# cpu-card-atmega328.net
KiCad netlist of a schematic drawn in EAGLE
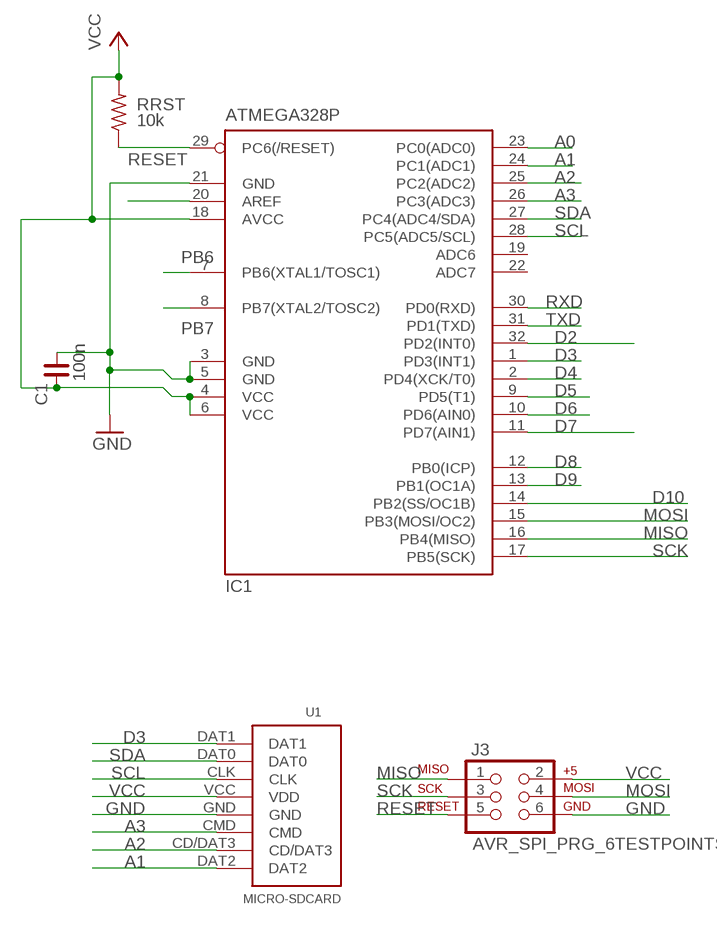
[diagram p0: schematic, sheet 1]

(export (version "E")
  (design (tool "Eeschema 10.0.6"))
  (components
    (comp (ref "C1")
      (value "100n")
      (footprint "eagle-import:C0603")
      (libsource (lib "eagle-import") (part "C_0603"))
    )
    (comp (ref "IC1")
      (value "ATMEGA328P")
      (footprint "eagle-import:TQFP32-08")
      (fields (field (name "MPN") "ATMEGA8-16AU"))
      (libsource (lib "eagle-import") (part "MEGA8-AI"))
    )
    (comp (ref "J3")
      (value "AVR_SPI_PRG_6TESTPOINTS")
      (footprint "eagle-import:2X3_TEST_POINTS")
      (libsource (lib "eagle-import") (part "AVR_SPI_PRG_6TESTPOINTS"))
    )
    (comp (ref "RRST")
      (value "10k")
      (footprint "eagle-import:R0603@1")
      (libsource (lib "eagle-import") (part "R-US_R0603"))
    )
    (comp (ref "U1")
      (value "MICRO-SDCARD")
      (footprint "eagle-import:MICRO-SDCARD")
      (libsource (lib "eagle-import") (part "MICRO-SDCARD"))
    )
  )
  (nets
    (net (code "1") (name "/A0") (class "Default")
      (node (ref "IC1") (pin "23") (pinfunction "PC0(ADC0)_23") (pintype "bidirectional"))
    )
    (net (code "2") (name "/A1") (class "Default")
      (node (ref "IC1") (pin "24") (pinfunction "PC1(ADC1)_24") (pintype "bidirectional"))
      (node (ref "U1") (pin "DAT2") (pinfunction "DAT2_DAT2") (pintype "bidirectional"))
    )
    (net (code "3") (name "/A2") (class "Default")
      (node (ref "IC1") (pin "25") (pinfunction "PC2(ADC2)_25") (pintype "bidirectional"))
      (node (ref "U1") (pin "CD/DAT3") (pinfunction "CD/DAT3_CD/DAT3") (pintype "bidirectional"))
    )
    (net (code "4") (name "/A3") (class "Default")
      (node (ref "IC1") (pin "26") (pinfunction "PC3(ADC3)_26") (pintype "bidirectional"))
      (node (ref "U1") (pin "CMD") (pinfunction "CMD_CMD") (pintype "bidirectional"))
    )
    (net (code "5") (name "/D2") (class "Default")
      (node (ref "IC1") (pin "32") (pinfunction "PD2(INT0)_32") (pintype "bidirectional"))
    )
    (net (code "6") (name "/D3") (class "Default")
      (node (ref "IC1") (pin "1") (pinfunction "PD3(INT1)_1") (pintype "bidirectional"))
      (node (ref "U1") (pin "DAT1") (pinfunction "DAT1_DAT1") (pintype "bidirectional"))
    )
    (net (code "7") (name "/D4") (class "Default")
      (node (ref "IC1") (pin "2") (pinfunction "PD4(XCK/T0)_2") (pintype "bidirectional"))
    )
    (net (code "8") (name "/D5") (class "Default")
      (node (ref "IC1") (pin "9") (pinfunction "PD5(T1)_9") (pintype "bidirectional"))
    )
    (net (code "9") (name "/D6") (class "Default")
      (node (ref "IC1") (pin "10") (pinfunction "PD6(AIN0)_10") (pintype "bidirectional"))
    )
    (net (code "10") (name "/D7") (class "Default")
      (node (ref "IC1") (pin "11") (pinfunction "PD7(AIN1)_11") (pintype "bidirectional"))
    )
    (net (code "11") (name "/D8") (class "Default")
      (node (ref "IC1") (pin "12") (pinfunction "PB0(ICP)_12") (pintype "bidirectional"))
    )
    (net (code "12") (name "/D9") (class "Default")
      (node (ref "IC1") (pin "13") (pinfunction "PB1(OC1A)_13") (pintype "bidirectional"))
    )
    (net (code "13") (name "/D10") (class "Default")
      (node (ref "IC1") (pin "14") (pinfunction "PB2(SS/OC1B)_14") (pintype "bidirectional"))
    )
    (net (code "14") (name "/MISO") (class "Default")
      (node (ref "IC1") (pin "16") (pinfunction "PB4(MISO)_16") (pintype "bidirectional"))
      (node (ref "J3") (pin "1") (pinfunction "1_1") (pintype "passive"))
    )
    (net (code "15") (name "/MOSI") (class "Default")
      (node (ref "IC1") (pin "15") (pinfunction "PB3(MOSI/OC2)_15") (pintype "bidirectional"))
      (node (ref "J3") (pin "4") (pinfunction "4_4") (pintype "passive"))
    )
    (net (code "16") (name "/PB6") (class "Default")
      (node (ref "IC1") (pin "7") (pinfunction "PB6(XTAL1/TOSC1)_7") (pintype "bidirectional"))
    )
    (net (code "17") (name "/PB7") (class "Default")
      (node (ref "IC1") (pin "8") (pinfunction "PB7(XTAL2/TOSC2)_8") (pintype "bidirectional"))
    )
    (net (code "18") (name "/RESET") (class "Default")
      (node (ref "IC1") (pin "29") (pinfunction "PC6(/RESET)_29") (pintype "bidirectional"))
      (node (ref "J3") (pin "5") (pinfunction "5_5") (pintype "passive"))
      (node (ref "RRST") (pin "1") (pinfunction "1_1") (pintype "passive"))
    )
    (net (code "19") (name "/RXD") (class "Default")
      (node (ref "IC1") (pin "30") (pinfunction "PD0(RXD)_30") (pintype "bidirectional"))
    )
    (net (code "20") (name "/SCK") (class "Default")
      (node (ref "IC1") (pin "17") (pinfunction "PB5(SCK)_17") (pintype "bidirectional"))
      (node (ref "J3") (pin "3") (pinfunction "3_3") (pintype "passive"))
    )
    (net (code "21") (name "/SCL") (class "Default")
      (node (ref "IC1") (pin "28") (pinfunction "PC5(ADC5/SCL)_28") (pintype "bidirectional"))
      (node (ref "U1") (pin "CLK") (pinfunction "CLK_CLK") (pintype "bidirectional"))
    )
    (net (code "22") (name "/SDA") (class "Default")
      (node (ref "IC1") (pin "27") (pinfunction "PC4(ADC4/SDA)_27") (pintype "bidirectional"))
      (node (ref "U1") (pin "DAT0") (pinfunction "DAT0_DAT0") (pintype "bidirectional"))
    )
    (net (code "23") (name "/TXD") (class "Default")
      (node (ref "IC1") (pin "31") (pinfunction "PD1(TXD)_31") (pintype "bidirectional"))
    )
    (net (code "24") (name "GND") (class "Default")
      (node (ref "C1") (pin "1") (pinfunction "1_1") (pintype "passive"))
      (node (ref "IC1") (pin "21") (pinfunction "GND_21") (pintype "power_in"))
      (node (ref "IC1") (pin "3") (pinfunction "GND_3") (pintype "power_in"))
      (node (ref "IC1") (pin "5") (pinfunction "GND_5") (pintype "power_in"))
      (node (ref "J3") (pin "6") (pinfunction "6_6") (pintype "passive"))
      (node (ref "U1") (pin "GND") (pinfunction "GND_GND") (pintype "bidirectional"))
    )
    (net (code "25") (name "VCC") (class "Default")
      (node (ref "C1") (pin "2") (pinfunction "2_2") (pintype "passive"))
      (node (ref "IC1") (pin "18") (pinfunction "AVCC_18") (pintype "power_in"))
      (node (ref "IC1") (pin "4") (pinfunction "VCC_4") (pintype "power_in"))
      (node (ref "IC1") (pin "6") (pinfunction "VCC_6") (pintype "power_in"))
      (node (ref "J3") (pin "2") (pinfunction "2_2") (pintype "passive"))
      (node (ref "RRST") (pin "2") (pinfunction "2_2") (pintype "passive"))
      (node (ref "U1") (pin "VCC") (pinfunction "VDD_VCC") (pintype "bidirectional"))
    )
    (net (code "26") (name "unconnected-(IC1-ADC6-Pad19)") (class "Default")
      (node (ref "IC1") (pin "19") (pinfunction "ADC6_19") (pintype "bidirectional"))
    )
    (net (code "27") (name "unconnected-(IC1-ADC7-Pad22)") (class "Default")
      (node (ref "IC1") (pin "22") (pinfunction "ADC7_22") (pintype "bidirectional"))
    )
    (net (code "28") (name "unconnected-(IC1-AREF-Pad20)") (class "Default")
      (node (ref "IC1") (pin "20") (pinfunction "AREF_20") (pintype "passive"))
    )
  )
)
